# schematic.net
KiCad netlist of a schematic drawn in EAGLE
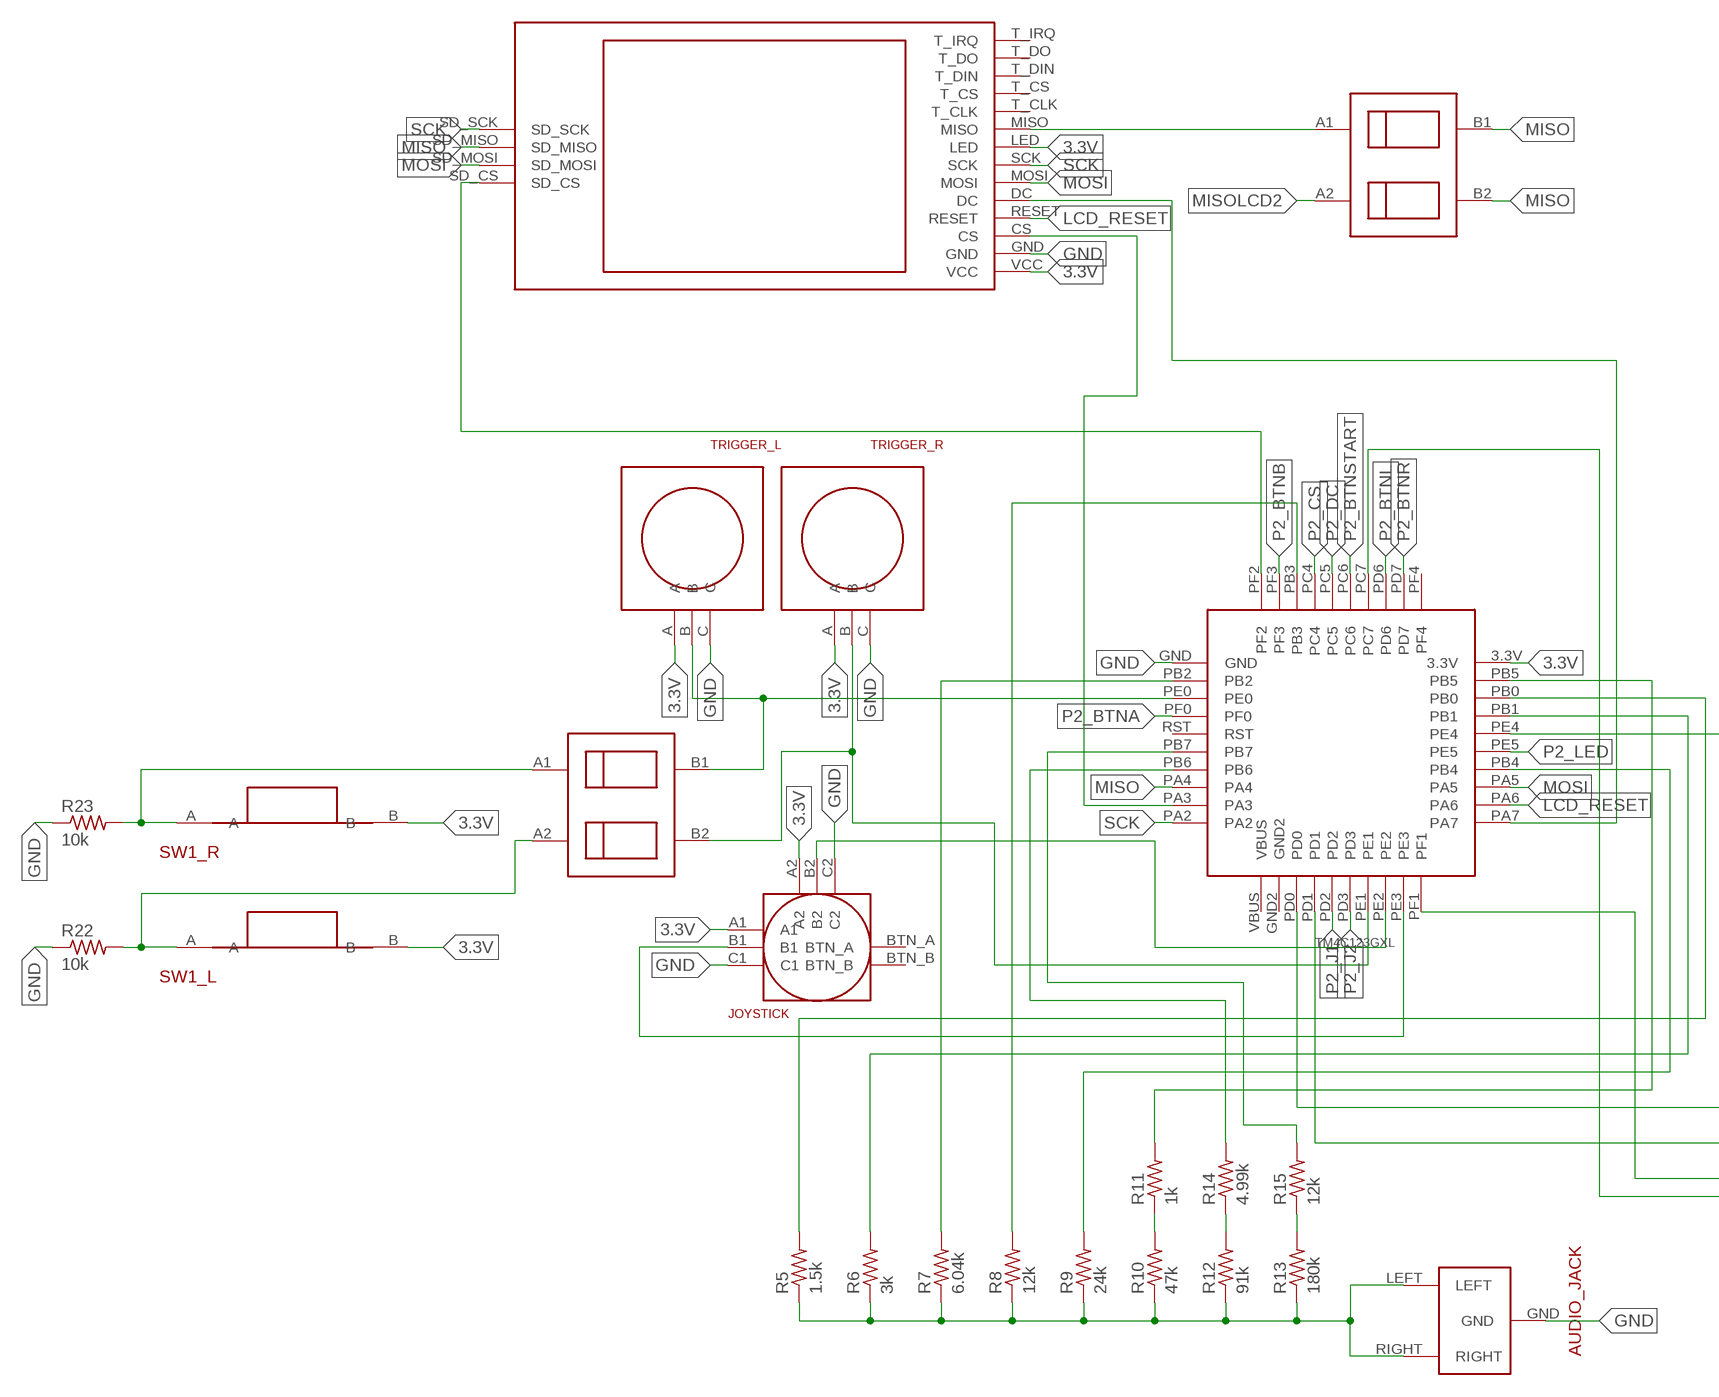
[diagram p0: schematic, sheet 1, part 1 of 2]
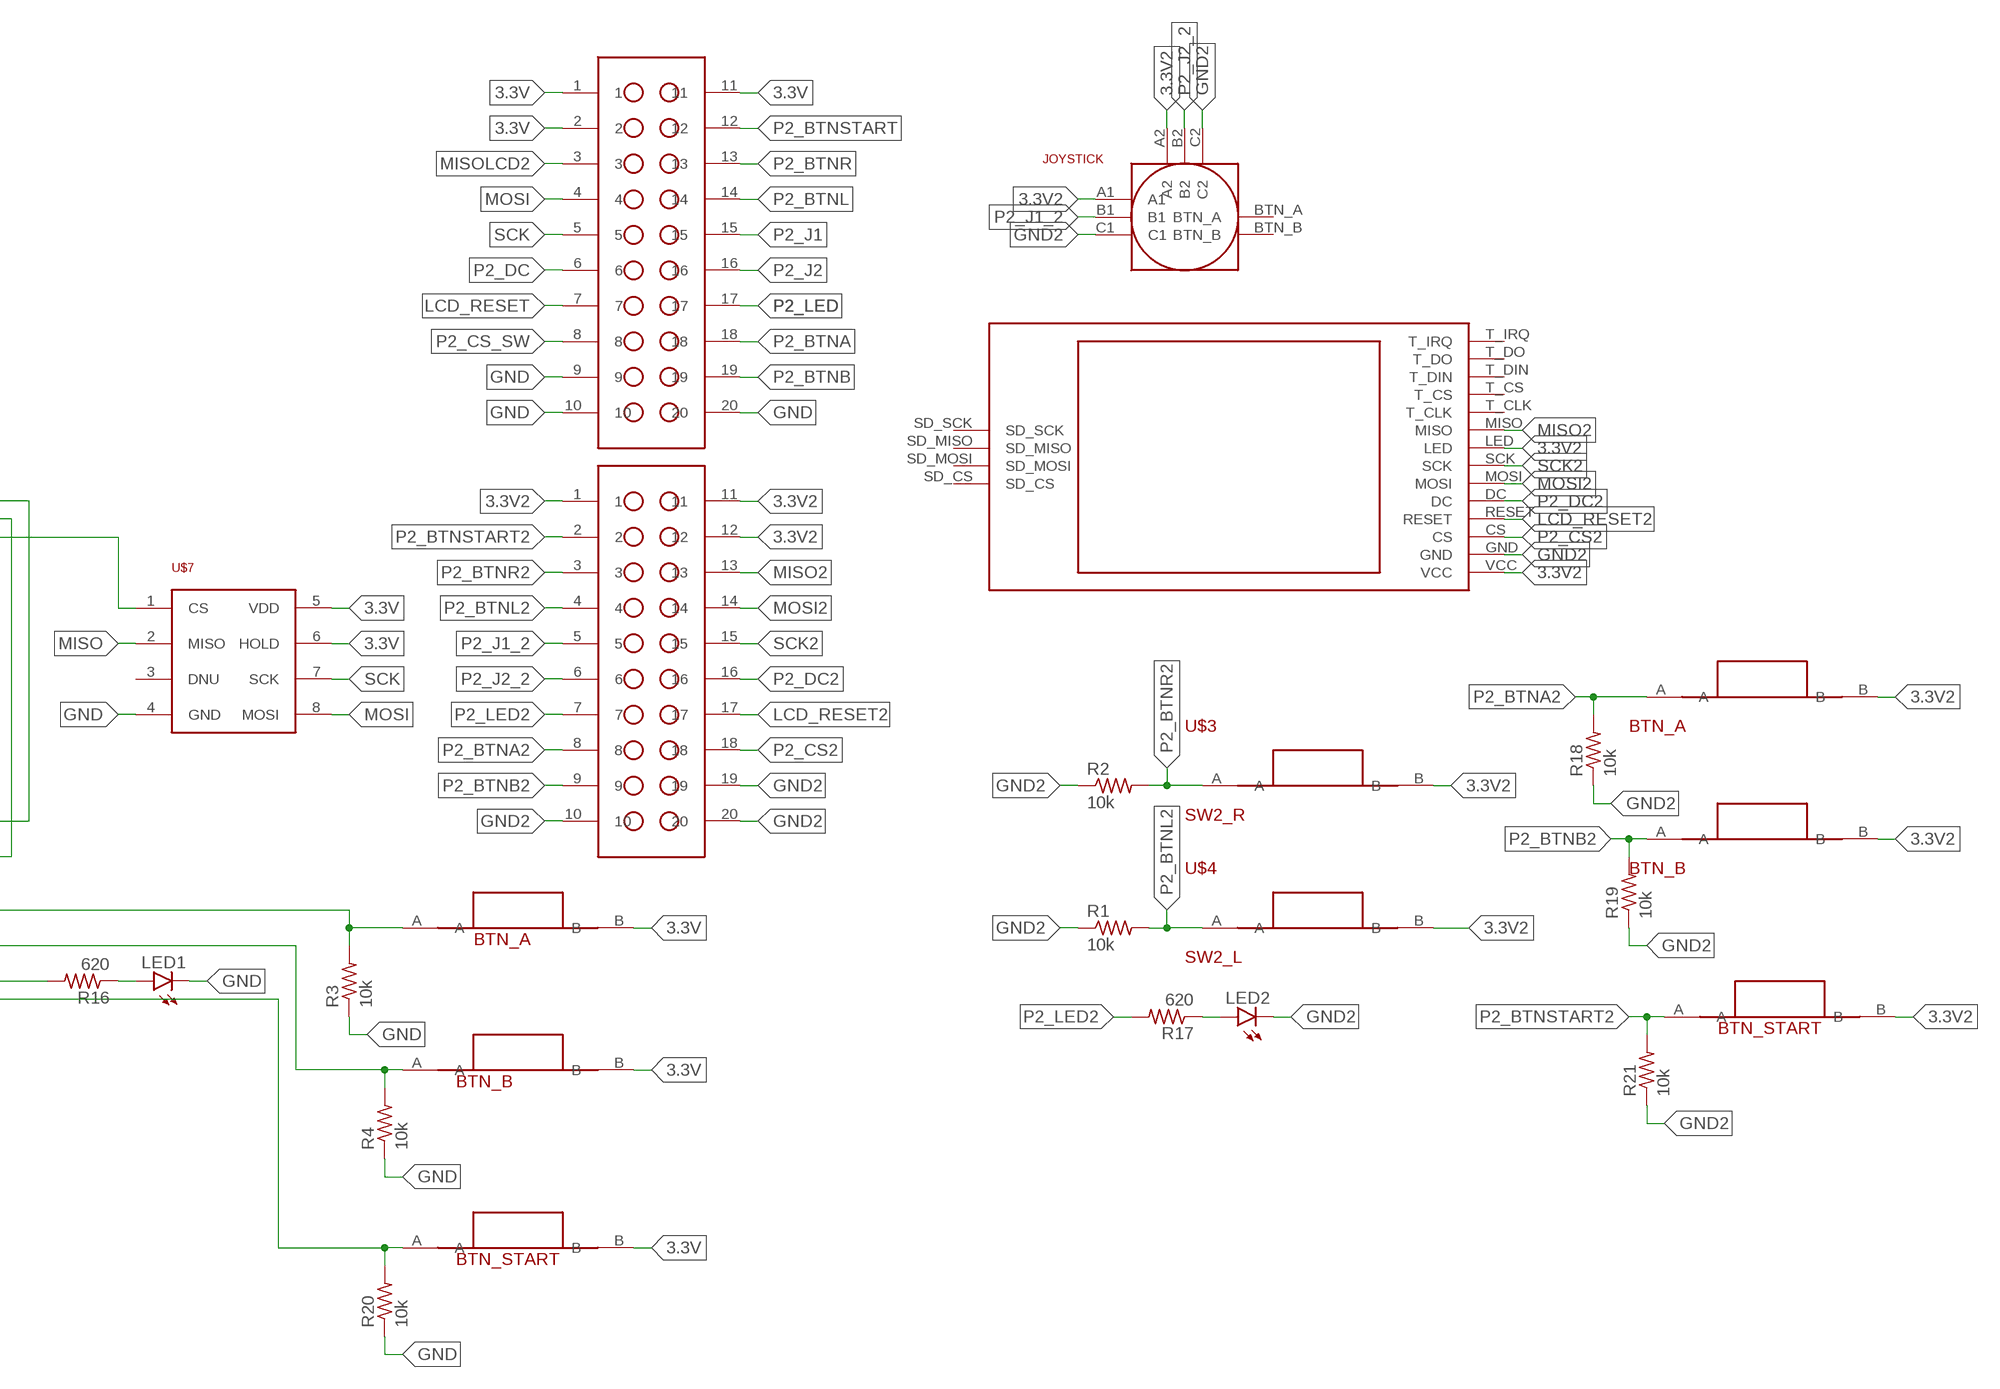
[diagram p1: schematic, sheet 1, part 2 of 2]

(export (version "E")
  (design (tool "Eeschema 10.0.6"))
  (components
    (comp (ref "LED1")
      (value "LEDCHIPLED_1206")
      (footprint "eagle-import:CHIPLED_1206")
      (libsource (lib "eagle-import") (part "LEDCHIPLED_1206"))
    )
    (comp (ref "LED2")
      (value "LEDCHIPLED_1206")
      (footprint "eagle-import:CHIPLED_1206")
      (libsource (lib "eagle-import") (part "LEDCHIPLED_1206"))
    )
    (comp (ref "P1_LCD")
      (value "ILI9341")
      (footprint "eagle-import:ILI9341")
      (libsource (lib "eagle-import") (part "ILI9341"))
    )
    (comp (ref "P2_LCD")
      (value "ILI9341")
      (footprint "eagle-import:ILI9341")
      (libsource (lib "eagle-import") (part "ILI9341"))
    )
    (comp (ref "R1")
      (value "10k")
      (footprint "eagle-import:R0805")
      (libsource (lib "eagle-import") (part "R-US_R0805"))
    )
    (comp (ref "R2")
      (value "10k")
      (footprint "eagle-import:R0805")
      (libsource (lib "eagle-import") (part "R-US_R0805"))
    )
    (comp (ref "R3")
      (value "10k")
      (footprint "eagle-import:R0805")
      (libsource (lib "eagle-import") (part "R-US_R0805"))
    )
    (comp (ref "R4")
      (value "10k")
      (footprint "eagle-import:R0805")
      (libsource (lib "eagle-import") (part "R-US_R0805"))
    )
    (comp (ref "R5")
      (value "1.5k")
      (footprint "eagle-import:R0805")
      (libsource (lib "eagle-import") (part "R-US_R0805"))
    )
    (comp (ref "R6")
      (value "3k")
      (footprint "eagle-import:R0805")
      (libsource (lib "eagle-import") (part "R-US_R0805"))
    )
    (comp (ref "R7")
      (value "6.04k")
      (footprint "eagle-import:R0805")
      (libsource (lib "eagle-import") (part "R-US_R0805"))
    )
    (comp (ref "R8")
      (value "12k")
      (footprint "eagle-import:R0805")
      (libsource (lib "eagle-import") (part "R-US_R0805"))
    )
    (comp (ref "R9")
      (value "24k")
      (footprint "eagle-import:R0805")
      (libsource (lib "eagle-import") (part "R-US_R0805"))
    )
    (comp (ref "R10")
      (value "47k")
      (footprint "eagle-import:R0805")
      (libsource (lib "eagle-import") (part "R-US_R0805"))
    )
    (comp (ref "R11")
      (value "1k")
      (footprint "eagle-import:R0805")
      (libsource (lib "eagle-import") (part "R-US_R0805"))
    )
    (comp (ref "R12")
      (value "91k")
      (footprint "eagle-import:R0805")
      (libsource (lib "eagle-import") (part "R-US_R0805"))
    )
    (comp (ref "R13")
      (value "180k")
      (footprint "eagle-import:R0805")
      (libsource (lib "eagle-import") (part "R-US_R0805"))
    )
    (comp (ref "R14")
      (value "4.99k")
      (footprint "eagle-import:R0805")
      (libsource (lib "eagle-import") (part "R-US_R0805"))
    )
    (comp (ref "R15")
      (value "12k")
      (footprint "eagle-import:R0805")
      (libsource (lib "eagle-import") (part "R-US_R0805"))
    )
    (comp (ref "R16")
      (value "620")
      (footprint "eagle-import:R0805")
      (libsource (lib "eagle-import") (part "R-US_R0805"))
    )
    (comp (ref "R17")
      (value "620")
      (footprint "eagle-import:R0805")
      (libsource (lib "eagle-import") (part "R-US_R0805"))
    )
    (comp (ref "R18")
      (value "10k")
      (footprint "eagle-import:R0805")
      (libsource (lib "eagle-import") (part "R-US_R0805"))
    )
    (comp (ref "R19")
      (value "10k")
      (footprint "eagle-import:R0805")
      (libsource (lib "eagle-import") (part "R-US_R0805"))
    )
    (comp (ref "R20")
      (value "10k")
      (footprint "eagle-import:R0805")
      (libsource (lib "eagle-import") (part "R-US_R0805"))
    )
    (comp (ref "R21")
      (value "10k")
      (footprint "eagle-import:R0805")
      (libsource (lib "eagle-import") (part "R-US_R0805"))
    )
    (comp (ref "R22")
      (value "10k")
      (footprint "eagle-import:R0805")
      (libsource (lib "eagle-import") (part "R-US_R0805"))
    )
    (comp (ref "R23")
      (value "10k")
      (footprint "eagle-import:R0805")
      (libsource (lib "eagle-import") (part "R-US_R0805"))
    )
    (comp (ref "U$1")
      (value "TM4C123GXL")
      (footprint "eagle-import:TM4C123GXL")
      (libsource (lib "eagle-import") (part "TM4C123GXL"))
    )
    (comp (ref "U$2")
      (value "JOYSTICK")
      (footprint "eagle-import:JOYSTICK")
      (libsource (lib "eagle-import") (part "JOYSTICK"))
    )
    (comp (ref "U$3")
      (value "SW2_R")
      (footprint "eagle-import:SW-1825968-2")
      (libsource (lib "eagle-import") (part "SW-1825968-2"))
    )
    (comp (ref "U$4")
      (value "SW2_L")
      (footprint "eagle-import:SW-1825968-2")
      (libsource (lib "eagle-import") (part "SW-1825968-2"))
    )
    (comp (ref "U$5")
      (value "TRIGGER_L")
      (footprint "eagle-import:TRIGGER_L")
      (libsource (lib "eagle-import") (part "TRIGGER_L"))
    )
    (comp (ref "U$6")
      (value "TRIGGER_R")
      (footprint "eagle-import:TRIGGER_R")
      (libsource (lib "eagle-import") (part "TRIGGER_R"))
    )
    (comp (ref "U$7")
      (value "IS62WVS5128FALL-16NLI")
      (footprint "eagle-import:SOIC127P600X144-8")
      (libsource (lib "eagle-import") (part "IS62WVS5128FALL-16NLI"))
    )
    (comp (ref "U$8")
      (value "BTN_A")
      (footprint "eagle-import:BUTTON")
      (libsource (lib "eagle-import") (part "BUTTON"))
    )
    (comp (ref "U$9")
      (value "BTN_B")
      (footprint "eagle-import:BUTTON")
      (libsource (lib "eagle-import") (part "BUTTON"))
    )
    (comp (ref "U$10")
      (value "AUDIO_JACK")
      (footprint "eagle-import:AUDIO_JACK")
      (libsource (lib "eagle-import") (part "AUDIO_JACK"))
    )
    (comp (ref "U$11")
      (value "10X2_HEADER")
      (footprint "eagle-import:10X2_HEADER")
      (libsource (lib "eagle-import") (part "10X2_HEADER"))
    )
    (comp (ref "U$12")
      (value "10X2_HEADER")
      (footprint "eagle-import:10X2_HEADER")
      (libsource (lib "eagle-import") (part "10X2_HEADER"))
    )
    (comp (ref "U$13")
      (value "JOYSTICK")
      (footprint "eagle-import:JOYSTICK")
      (libsource (lib "eagle-import") (part "JOYSTICK"))
    )
    (comp (ref "U$14")
      (value "BTN_A")
      (footprint "eagle-import:BUTTON")
      (libsource (lib "eagle-import") (part "BUTTON"))
    )
    (comp (ref "U$15")
      (value "BTN_B")
      (footprint "eagle-import:BUTTON")
      (libsource (lib "eagle-import") (part "BUTTON"))
    )
    (comp (ref "U$16")
      (value "BTN_START")
      (footprint "eagle-import:BUTTON")
      (libsource (lib "eagle-import") (part "BUTTON"))
    )
    (comp (ref "U$17")
      (value "BTN_START")
      (footprint "eagle-import:BUTTON")
      (libsource (lib "eagle-import") (part "BUTTON"))
    )
    (comp (ref "U$18")
      (value "SW1_R")
      (footprint "eagle-import:SW-1825968-2")
      (libsource (lib "eagle-import") (part "SW-1825968-2"))
    )
    (comp (ref "U$19")
      (value "SW1_L")
      (footprint "eagle-import:SW-1825968-2")
      (libsource (lib "eagle-import") (part "SW-1825968-2"))
    )
    (comp (ref "U$20")
      (value "DIPSW-2")
      (footprint "eagle-import:DIPSW-2")
      (libsource (lib "eagle-import") (part "DIPSW-2"))
    )
    (comp (ref "U$21")
      (value "DIPSW-2")
      (footprint "eagle-import:DIPSW-2")
      (libsource (lib "eagle-import") (part "DIPSW-2"))
    )
  )
  (nets
    (net (code "1") (name "3.3V") (class "Default")
      (node (ref "P1_LCD") (pin "LED") (pinfunction "LED_LED") (pintype "bidirectional"))
      (node (ref "P1_LCD") (pin "VCC") (pinfunction "VCC_VCC") (pintype "bidirectional"))
      (node (ref "U$1") (pin "3.3V") (pinfunction "3.3V_3.3V") (pintype "bidirectional"))
      (node (ref "U$11") (pin "1") (pinfunction "1_1") (pintype "bidirectional"))
      (node (ref "U$11") (pin "11") (pinfunction "11_11") (pintype "bidirectional"))
      (node (ref "U$11") (pin "2") (pinfunction "2_2") (pintype "bidirectional"))
      (node (ref "U$16") (pin "B") (pinfunction "B_B") (pintype "bidirectional"))
      (node (ref "U$18") (pin "B") (pinfunction "B_B") (pintype "bidirectional"))
      (node (ref "U$19") (pin "B") (pinfunction "B_B") (pintype "bidirectional"))
      (node (ref "U$2") (pin "A1") (pinfunction "A1_A1") (pintype "bidirectional"))
      (node (ref "U$2") (pin "A2") (pinfunction "A2_A2") (pintype "bidirectional"))
      (node (ref "U$5") (pin "A") (pinfunction "A_A") (pintype "bidirectional"))
      (node (ref "U$6") (pin "A") (pinfunction "A_A") (pintype "bidirectional"))
      (node (ref "U$7") (pin "5") (pinfunction "VDD_5") (pintype "bidirectional"))
      (node (ref "U$7") (pin "6") (pinfunction "HOLD_6") (pintype "bidirectional"))
      (node (ref "U$8") (pin "B") (pinfunction "B_B") (pintype "bidirectional"))
      (node (ref "U$9") (pin "B") (pinfunction "B_B") (pintype "bidirectional"))
    )
    (net (code "2") (name "3.3V2") (class "Default")
      (node (ref "P2_LCD") (pin "LED") (pinfunction "LED_LED") (pintype "bidirectional"))
      (node (ref "P2_LCD") (pin "VCC") (pinfunction "VCC_VCC") (pintype "bidirectional"))
      (node (ref "U$12") (pin "1") (pinfunction "1_1") (pintype "bidirectional"))
      (node (ref "U$12") (pin "11") (pinfunction "11_11") (pintype "bidirectional"))
      (node (ref "U$12") (pin "12") (pinfunction "12_12") (pintype "bidirectional"))
      (node (ref "U$13") (pin "A1") (pinfunction "A1_A1") (pintype "bidirectional"))
      (node (ref "U$13") (pin "A2") (pinfunction "A2_A2") (pintype "bidirectional"))
      (node (ref "U$14") (pin "B") (pinfunction "B_B") (pintype "bidirectional"))
      (node (ref "U$15") (pin "B") (pinfunction "B_B") (pintype "bidirectional"))
      (node (ref "U$17") (pin "B") (pinfunction "B_B") (pintype "bidirectional"))
      (node (ref "U$3") (pin "B") (pinfunction "B_B") (pintype "bidirectional"))
      (node (ref "U$4") (pin "B") (pinfunction "B_B") (pintype "bidirectional"))
    )
    (net (code "3") (name "GND") (class "Default")
      (node (ref "LED1") (pin "C") (pinfunction "C_C") (pintype "passive"))
      (node (ref "P1_LCD") (pin "GND") (pinfunction "GND_GND") (pintype "bidirectional"))
      (node (ref "R20") (pin "1") (pinfunction "1_1") (pintype "passive"))
      (node (ref "R22") (pin "1") (pinfunction "1_1") (pintype "passive"))
      (node (ref "R23") (pin "1") (pinfunction "1_1") (pintype "passive"))
      (node (ref "R3") (pin "1") (pinfunction "1_1") (pintype "passive"))
      (node (ref "R4") (pin "1") (pinfunction "1_1") (pintype "passive"))
      (node (ref "U$1") (pin "GND") (pinfunction "GND_GND") (pintype "bidirectional"))
      (node (ref "U$10") (pin "GND") (pinfunction "GND_GND") (pintype "bidirectional"))
      (node (ref "U$11") (pin "10") (pinfunction "10_10") (pintype "bidirectional"))
      (node (ref "U$11") (pin "20") (pinfunction "20_20") (pintype "bidirectional"))
      (node (ref "U$11") (pin "9") (pinfunction "9_9") (pintype "bidirectional"))
      (node (ref "U$2") (pin "C1") (pinfunction "C1_C1") (pintype "bidirectional"))
      (node (ref "U$2") (pin "C2") (pinfunction "C2_C2") (pintype "bidirectional"))
      (node (ref "U$5") (pin "C") (pinfunction "C_C") (pintype "bidirectional"))
      (node (ref "U$6") (pin "C") (pinfunction "C_C") (pintype "bidirectional"))
      (node (ref "U$7") (pin "4") (pinfunction "GND_4") (pintype "bidirectional"))
    )
    (net (code "4") (name "GND2") (class "Default")
      (node (ref "LED2") (pin "C") (pinfunction "C_C") (pintype "passive"))
      (node (ref "P2_LCD") (pin "GND") (pinfunction "GND_GND") (pintype "bidirectional"))
      (node (ref "R1") (pin "1") (pinfunction "1_1") (pintype "passive"))
      (node (ref "R18") (pin "1") (pinfunction "1_1") (pintype "passive"))
      (node (ref "R19") (pin "1") (pinfunction "1_1") (pintype "passive"))
      (node (ref "R2") (pin "1") (pinfunction "1_1") (pintype "passive"))
      (node (ref "R21") (pin "1") (pinfunction "1_1") (pintype "passive"))
      (node (ref "U$12") (pin "10") (pinfunction "10_10") (pintype "bidirectional"))
      (node (ref "U$12") (pin "19") (pinfunction "19_19") (pintype "bidirectional"))
      (node (ref "U$12") (pin "20") (pinfunction "20_20") (pintype "bidirectional"))
      (node (ref "U$13") (pin "C1") (pinfunction "C1_C1") (pintype "bidirectional"))
      (node (ref "U$13") (pin "C2") (pinfunction "C2_C2") (pintype "bidirectional"))
    )
    (net (code "5") (name "LCD_RESET") (class "Default")
      (node (ref "P1_LCD") (pin "RESET") (pinfunction "RESET_RESET") (pintype "bidirectional"))
      (node (ref "U$1") (pin "PA6") (pinfunction "PA6_PA6") (pintype "bidirectional"))
      (node (ref "U$11") (pin "7") (pinfunction "7_7") (pintype "bidirectional"))
    )
    (net (code "6") (name "LCD_RESET2") (class "Default")
      (node (ref "P2_LCD") (pin "RESET") (pinfunction "RESET_RESET") (pintype "bidirectional"))
      (node (ref "U$12") (pin "17") (pinfunction "17_17") (pintype "bidirectional"))
    )
    (net (code "7") (name "MISO") (class "Default")
      (node (ref "P1_LCD") (pin "SD_MISO") (pinfunction "SD_MISO_SD_MISO") (pintype "bidirectional"))
      (node (ref "U$1") (pin "PA4") (pinfunction "PA4_PA4") (pintype "bidirectional"))
      (node (ref "U$21") (pin "B1") (pinfunction "B1_B1") (pintype "passive"))
      (node (ref "U$21") (pin "B2") (pinfunction "B2_B2") (pintype "passive"))
      (node (ref "U$7") (pin "2") (pinfunction "MISO_2") (pintype "bidirectional"))
    )
    (net (code "8") (name "MISO2") (class "Default")
      (node (ref "P2_LCD") (pin "MISO") (pinfunction "MISO_MISO") (pintype "bidirectional"))
      (node (ref "U$12") (pin "13") (pinfunction "13_13") (pintype "bidirectional"))
    )
    (net (code "9") (name "MISOLCD2") (class "Default")
      (node (ref "U$11") (pin "3") (pinfunction "3_3") (pintype "bidirectional"))
      (node (ref "U$21") (pin "A2") (pinfunction "A2_A2") (pintype "passive"))
    )
    (net (code "10") (name "MOSI") (class "Default")
      (node (ref "P1_LCD") (pin "MOSI") (pinfunction "MOSI_MOSI") (pintype "bidirectional"))
      (node (ref "P1_LCD") (pin "SD_MOSI") (pinfunction "SD_MOSI_SD_MOSI") (pintype "bidirectional"))
      (node (ref "U$1") (pin "PA5") (pinfunction "PA5_PA5") (pintype "bidirectional"))
      (node (ref "U$11") (pin "4") (pinfunction "4_4") (pintype "bidirectional"))
      (node (ref "U$7") (pin "8") (pinfunction "MOSI_8") (pintype "bidirectional"))
    )
    (net (code "11") (name "MOSI2") (class "Default")
      (node (ref "P2_LCD") (pin "MOSI") (pinfunction "MOSI_MOSI") (pintype "bidirectional"))
      (node (ref "U$12") (pin "14") (pinfunction "14_14") (pintype "bidirectional"))
    )
    (net (code "12") (name "Net-(LED1-PadA)") (class "Default")
      (node (ref "LED1") (pin "A") (pinfunction "A_A") (pintype "passive"))
      (node (ref "R16") (pin "1") (pinfunction "1_1") (pintype "passive"))
    )
    (net (code "13") (name "Net-(LED2-PadA)") (class "Default")
      (node (ref "LED2") (pin "A") (pinfunction "A_A") (pintype "passive"))
      (node (ref "R17") (pin "1") (pinfunction "1_1") (pintype "passive"))
    )
    (net (code "14") (name "Net-(P1_LCD-PadCS)") (class "Default")
      (node (ref "P1_LCD") (pin "CS") (pinfunction "CS_CS") (pintype "bidirectional"))
      (node (ref "U$1") (pin "PA3") (pinfunction "PA3_PA3") (pintype "bidirectional"))
    )
    (net (code "15") (name "Net-(P1_LCD-PadDC)") (class "Default")
      (node (ref "P1_LCD") (pin "DC") (pinfunction "DC_DC") (pintype "bidirectional"))
      (node (ref "U$1") (pin "PA7") (pinfunction "PA7_PA7") (pintype "bidirectional"))
    )
    (net (code "16") (name "Net-(P1_LCD-PadMISO)") (class "Default")
      (node (ref "P1_LCD") (pin "MISO") (pinfunction "MISO_MISO") (pintype "bidirectional"))
      (node (ref "U$21") (pin "A1") (pinfunction "A1_A1") (pintype "passive"))
    )
    (net (code "17") (name "Net-(P1_LCD-PadSD_CS)") (class "Default")
      (node (ref "P1_LCD") (pin "SD_CS") (pinfunction "SD_CS_SD_CS") (pintype "bidirectional"))
      (node (ref "U$1") (pin "PF2") (pinfunction "PF2_PF2") (pintype "bidirectional"))
    )
    (net (code "18") (name "Net-(R3-Pad2)") (class "Default")
      (node (ref "R3") (pin "2") (pinfunction "2_2") (pintype "passive"))
      (node (ref "U$1") (pin "PD0") (pinfunction "PD0_PD0") (pintype "bidirectional"))
      (node (ref "U$8") (pin "A") (pinfunction "A_A") (pintype "bidirectional"))
    )
    (net (code "19") (name "Net-(R4-Pad2)") (class "Default")
      (node (ref "R4") (pin "2") (pinfunction "2_2") (pintype "passive"))
      (node (ref "U$1") (pin "PD1") (pinfunction "PD1_PD1") (pintype "bidirectional"))
      (node (ref "U$9") (pin "A") (pinfunction "A_A") (pintype "bidirectional"))
    )
    (net (code "20") (name "Net-(R5-Pad2)") (class "Default")
      (node (ref "R5") (pin "2") (pinfunction "2_2") (pintype "passive"))
      (node (ref "U$1") (pin "PB0") (pinfunction "PB0_PB0") (pintype "bidirectional"))
    )
    (net (code "21") (name "Net-(R6-Pad2)") (class "Default")
      (node (ref "R6") (pin "2") (pinfunction "2_2") (pintype "passive"))
      (node (ref "U$1") (pin "PB1") (pinfunction "PB1_PB1") (pintype "bidirectional"))
    )
    (net (code "22") (name "Net-(R7-Pad2)") (class "Default")
      (node (ref "R7") (pin "2") (pinfunction "2_2") (pintype "passive"))
      (node (ref "U$1") (pin "PB2") (pinfunction "PB2_PB2") (pintype "bidirectional"))
    )
    (net (code "23") (name "Net-(R8-Pad2)") (class "Default")
      (node (ref "R8") (pin "2") (pinfunction "2_2") (pintype "passive"))
      (node (ref "U$1") (pin "PB3") (pinfunction "PB3_PB3") (pintype "bidirectional"))
    )
    (net (code "24") (name "Net-(R9-Pad2)") (class "Default")
      (node (ref "R9") (pin "2") (pinfunction "2_2") (pintype "passive"))
      (node (ref "U$1") (pin "PB4") (pinfunction "PB4_PB4") (pintype "bidirectional"))
    )
    (net (code "25") (name "Net-(R10-Pad1)") (class "Default")
      (node (ref "R10") (pin "1") (pinfunction "1_1") (pintype "passive"))
      (node (ref "R12") (pin "1") (pinfunction "1_1") (pintype "passive"))
      (node (ref "R13") (pin "1") (pinfunction "1_1") (pintype "passive"))
      (node (ref "R5") (pin "1") (pinfunction "1_1") (pintype "passive"))
      (node (ref "R6") (pin "1") (pinfunction "1_1") (pintype "passive"))
      (node (ref "R7") (pin "1") (pinfunction "1_1") (pintype "passive"))
      (node (ref "R8") (pin "1") (pinfunction "1_1") (pintype "passive"))
      (node (ref "R9") (pin "1") (pinfunction "1_1") (pintype "passive"))
      (node (ref "U$10") (pin "LEFT") (pinfunction "LEFT_LEFT") (pintype "bidirectional"))
      (node (ref "U$10") (pin "RIGHT") (pinfunction "RIGHT_RIGHT") (pintype "bidirectional"))
    )
    (net (code "26") (name "Net-(R10-Pad2)") (class "Default")
      (node (ref "R10") (pin "2") (pinfunction "2_2") (pintype "passive"))
      (node (ref "R11") (pin "1") (pinfunction "1_1") (pintype "passive"))
    )
    (net (code "27") (name "Net-(R11-Pad2)") (class "Default")
      (node (ref "R11") (pin "2") (pinfunction "2_2") (pintype "passive"))
      (node (ref "U$1") (pin "PB5") (pinfunction "PB5_PB5") (pintype "bidirectional"))
    )
    (net (code "28") (name "Net-(R12-Pad2)") (class "Default")
      (node (ref "R12") (pin "2") (pinfunction "2_2") (pintype "passive"))
      (node (ref "R14") (pin "1") (pinfunction "1_1") (pintype "passive"))
    )
    (net (code "29") (name "Net-(R13-Pad2)") (class "Default")
      (node (ref "R13") (pin "2") (pinfunction "2_2") (pintype "passive"))
      (node (ref "R15") (pin "1") (pinfunction "1_1") (pintype "passive"))
    )
    (net (code "30") (name "Net-(R14-Pad2)") (class "Default")
      (node (ref "R14") (pin "2") (pinfunction "2_2") (pintype "passive"))
      (node (ref "U$1") (pin "PB6") (pinfunction "PB6_PB6") (pintype "bidirectional"))
    )
    (net (code "31") (name "Net-(R15-Pad2)") (class "Default")
      (node (ref "R15") (pin "2") (pinfunction "2_2") (pintype "passive"))
      (node (ref "U$1") (pin "PB7") (pinfunction "PB7_PB7") (pintype "bidirectional"))
    )
    (net (code "32") (name "Net-(R16-Pad2)") (class "Default")
      (node (ref "R16") (pin "2") (pinfunction "2_2") (pintype "passive"))
      (node (ref "U$1") (pin "PF1") (pinfunction "PF1_PF1") (pintype "bidirectional"))
    )
    (net (code "33") (name "Net-(R20-Pad2)") (class "Default")
      (node (ref "R20") (pin "2") (pinfunction "2_2") (pintype "passive"))
      (node (ref "U$1") (pin "PC7") (pinfunction "PC7_PC7") (pintype "bidirectional"))
      (node (ref "U$16") (pin "A") (pinfunction "A_A") (pintype "bidirectional"))
    )
    (net (code "34") (name "Net-(R22-Pad2)") (class "Default")
      (node (ref "R22") (pin "2") (pinfunction "2_2") (pintype "passive"))
      (node (ref "U$19") (pin "A") (pinfunction "A_A") (pintype "bidirectional"))
      (node (ref "U$20") (pin "A2") (pinfunction "A2_A2") (pintype "passive"))
    )
    (net (code "35") (name "Net-(R23-Pad2)") (class "Default")
      (node (ref "R23") (pin "2") (pinfunction "2_2") (pintype "passive"))
      (node (ref "U$18") (pin "A") (pinfunction "A_A") (pintype "bidirectional"))
      (node (ref "U$20") (pin "A1") (pinfunction "A1_A1") (pintype "passive"))
    )
    (net (code "36") (name "Net-(U$1-PadPE0)") (class "Default")
      (node (ref "U$1") (pin "PE0") (pinfunction "PE0_PE0") (pintype "bidirectional"))
      (node (ref "U$20") (pin "B1") (pinfunction "B1_B1") (pintype "passive"))
      (node (ref "U$5") (pin "B") (pinfunction "B_B") (pintype "bidirectional"))
    )
    (net (code "37") (name "Net-(U$1-PadPE1)") (class "Default")
      (node (ref "U$1") (pin "PE1") (pinfunction "PE1_PE1") (pintype "bidirectional"))
      (node (ref "U$20") (pin "B2") (pinfunction "B2_B2") (pintype "passive"))
      (node (ref "U$6") (pin "B") (pinfunction "B_B") (pintype "bidirectional"))
    )
    (net (code "38") (name "Net-(U$1-PadPE2)") (class "Default")
      (node (ref "U$1") (pin "PE2") (pinfunction "PE2_PE2") (pintype "bidirectional"))
      (node (ref "U$2") (pin "B2") (pinfunction "B2_B2") (pintype "bidirectional"))
    )
    (net (code "39") (name "Net-(U$1-PadPE3)") (class "Default")
      (node (ref "U$1") (pin "PE3") (pinfunction "PE3_PE3") (pintype "bidirectional"))
      (node (ref "U$2") (pin "B1") (pinfunction "B1_B1") (pintype "bidirectional"))
    )
    (net (code "40") (name "Net-(U$7-CS)") (class "Default")
      (node (ref "U$1") (pin "PE4") (pinfunction "PE4_PE4") (pintype "bidirectional"))
      (node (ref "U$7") (pin "1") (pinfunction "CS_1") (pintype "bidirectional"))
    )
    (net (code "41") (name "P2_BTNA") (class "Default")
      (node (ref "U$1") (pin "PF0") (pinfunction "PF0_PF0") (pintype "bidirectional"))
      (node (ref "U$11") (pin "18") (pinfunction "18_18") (pintype "bidirectional"))
    )
    (net (code "42") (name "P2_BTNA2") (class "Default")
      (node (ref "R18") (pin "2") (pinfunction "2_2") (pintype "passive"))
      (node (ref "U$12") (pin "8") (pinfunction "8_8") (pintype "bidirectional"))
      (node (ref "U$14") (pin "A") (pinfunction "A_A") (pintype "bidirectional"))
    )
    (net (code "43") (name "P2_BTNB") (class "Default")
      (node (ref "U$1") (pin "PF3") (pinfunction "PF3_PF3") (pintype "bidirectional"))
      (node (ref "U$11") (pin "19") (pinfunction "19_19") (pintype "bidirectional"))
    )
    (net (code "44") (name "P2_BTNB2") (class "Default")
      (node (ref "R19") (pin "2") (pinfunction "2_2") (pintype "passive"))
      (node (ref "U$12") (pin "9") (pinfunction "9_9") (pintype "bidirectional"))
      (node (ref "U$15") (pin "A") (pinfunction "A_A") (pintype "bidirectional"))
    )
    (net (code "45") (name "P2_BTNL") (class "Default")
      (node (ref "U$1") (pin "PD6") (pinfunction "PD6_PD6") (pintype "bidirectional"))
      (node (ref "U$11") (pin "14") (pinfunction "14_14") (pintype "bidirectional"))
    )
    (net (code "46") (name "P2_BTNL2") (class "Default")
      (node (ref "R1") (pin "2") (pinfunction "2_2") (pintype "passive"))
      (node (ref "U$12") (pin "4") (pinfunction "4_4") (pintype "bidirectional"))
      (node (ref "U$4") (pin "A") (pinfunction "A_A") (pintype "bidirectional"))
    )
    (net (code "47") (name "P2_BTNR") (class "Default")
      (node (ref "U$1") (pin "PD7") (pinfunction "PD7_PD7") (pintype "bidirectional"))
      (node (ref "U$11") (pin "13") (pinfunction "13_13") (pintype "bidirectional"))
    )
    (net (code "48") (name "P2_BTNR2") (class "Default")
      (node (ref "R2") (pin "2") (pinfunction "2_2") (pintype "passive"))
      (node (ref "U$12") (pin "3") (pinfunction "3_3") (pintype "bidirectional"))
      (node (ref "U$3") (pin "A") (pinfunction "A_A") (pintype "bidirectional"))
    )
    (net (code "49") (name "P2_BTNSTART") (class "Default")
      (node (ref "U$1") (pin "PC6") (pinfunction "PC6_PC6") (pintype "bidirectional"))
      (node (ref "U$11") (pin "12") (pinfunction "12_12") (pintype "bidirectional"))
    )
    (net (code "50") (name "P2_BTNSTART2") (class "Default")
      (node (ref "R21") (pin "2") (pinfunction "2_2") (pintype "passive"))
      (node (ref "U$12") (pin "2") (pinfunction "2_2") (pintype "bidirectional"))
      (node (ref "U$17") (pin "A") (pinfunction "A_A") (pintype "bidirectional"))
    )
    (net (code "51") (name "P2_CS") (class "Default")
      (node (ref "U$1") (pin "PC4") (pinfunction "PC4_PC4") (pintype "bidirectional"))
    )
    (net (code "52") (name "P2_CS2") (class "Default")
      (node (ref "P2_LCD") (pin "CS") (pinfunction "CS_CS") (pintype "bidirectional"))
      (node (ref "U$12") (pin "18") (pinfunction "18_18") (pintype "bidirectional"))
    )
    (net (code "53") (name "P2_CS_SW") (class "Default")
      (node (ref "U$11") (pin "8") (pinfunction "8_8") (pintype "bidirectional"))
    )
    (net (code "54") (name "P2_DC") (class "Default")
      (node (ref "U$1") (pin "PC5") (pinfunction "PC5_PC5") (pintype "bidirectional"))
      (node (ref "U$11") (pin "6") (pinfunction "6_6") (pintype "bidirectional"))
    )
    (net (code "55") (name "P2_DC2") (class "Default")
      (node (ref "P2_LCD") (pin "DC") (pinfunction "DC_DC") (pintype "bidirectional"))
      (node (ref "U$12") (pin "16") (pinfunction "16_16") (pintype "bidirectional"))
    )
    (net (code "56") (name "P2_J1") (class "Default")
      (node (ref "U$1") (pin "PD2") (pinfunction "PD2_PD2") (pintype "bidirectional"))
      (node (ref "U$11") (pin "15") (pinfunction "15_15") (pintype "bidirectional"))
    )
    (net (code "57") (name "P2_J1_2") (class "Default")
      (node (ref "U$12") (pin "5") (pinfunction "5_5") (pintype "bidirectional"))
      (node (ref "U$13") (pin "B1") (pinfunction "B1_B1") (pintype "bidirectional"))
    )
    (net (code "58") (name "P2_J2") (class "Default")
      (node (ref "U$1") (pin "PD3") (pinfunction "PD3_PD3") (pintype "bidirectional"))
      (node (ref "U$11") (pin "16") (pinfunction "16_16") (pintype "bidirectional"))
    )
    (net (code "59") (name "P2_J2_2") (class "Default")
      (node (ref "U$12") (pin "6") (pinfunction "6_6") (pintype "bidirectional"))
      (node (ref "U$13") (pin "B2") (pinfunction "B2_B2") (pintype "bidirectional"))
    )
    (net (code "60") (name "P2_LED") (class "Default")
      (node (ref "U$1") (pin "PE5") (pinfunction "PE5_PE5") (pintype "bidirectional"))
      (node (ref "U$11") (pin "17") (pinfunction "17_17") (pintype "bidirectional"))
    )
    (net (code "61") (name "P2_LED2") (class "Default")
      (node (ref "R17") (pin "2") (pinfunction "2_2") (pintype "passive"))
      (node (ref "U$12") (pin "7") (pinfunction "7_7") (pintype "bidirectional"))
    )
    (net (code "62") (name "SCK") (class "Default")
      (node (ref "P1_LCD") (pin "SCK") (pinfunction "SCK_SCK") (pintype "bidirectional"))
      (node (ref "P1_LCD") (pin "SD_SCK") (pinfunction "SD_SCK_SD_SCK") (pintype "bidirectional"))
      (node (ref "U$1") (pin "PA2") (pinfunction "PA2_PA2") (pintype "bidirectional"))
      (node (ref "U$11") (pin "5") (pinfunction "5_5") (pintype "bidirectional"))
      (node (ref "U$7") (pin "7") (pinfunction "SCK_7") (pintype "bidirectional"))
    )
    (net (code "63") (name "SCK2") (class "Default")
      (node (ref "P2_LCD") (pin "SCK") (pinfunction "SCK_SCK") (pintype "bidirectional"))
      (node (ref "U$12") (pin "15") (pinfunction "15_15") (pintype "bidirectional"))
    )
    (net (code "64") (name "unconnected-(P1_LCD-PadT_CLK)") (class "Default")
      (node (ref "P1_LCD") (pin "T_CLK") (pinfunction "T_CLK_T_CLK") (pintype "bidirectional"))
    )
    (net (code "65") (name "unconnected-(P1_LCD-PadT_CS)") (class "Default")
      (node (ref "P1_LCD") (pin "T_CS") (pinfunction "T_CS_T_CS") (pintype "bidirectional"))
    )
    (net (code "66") (name "unconnected-(P1_LCD-PadT_DIN)") (class "Default")
      (node (ref "P1_LCD") (pin "T_DIN") (pinfunction "T_DIN_T_DIN") (pintype "bidirectional"))
    )
    (net (code "67") (name "unconnected-(P1_LCD-PadT_DO)") (class "Default")
      (node (ref "P1_LCD") (pin "T_DO") (pinfunction "T_DO_T_DO") (pintype "bidirectional"))
    )
    (net (code "68") (name "unconnected-(P1_LCD-PadT_IRQ)") (class "Default")
      (node (ref "P1_LCD") (pin "T_IRQ") (pinfunction "T_IRQ_T_IRQ") (pintype "bidirectional"))
    )
    (net (code "69") (name "unconnected-(P2_LCD-PadSD_CS)") (class "Default")
      (node (ref "P2_LCD") (pin "SD_CS") (pinfunction "SD_CS_SD_CS") (pintype "bidirectional"))
    )
    (net (code "70") (name "unconnected-(P2_LCD-PadSD_MISO)") (class "Default")
      (node (ref "P2_LCD") (pin "SD_MISO") (pinfunction "SD_MISO_SD_MISO") (pintype "bidirectional"))
    )
    (net (code "71") (name "unconnected-(P2_LCD-PadSD_MOSI)") (class "Default")
      (node (ref "P2_LCD") (pin "SD_MOSI") (pinfunction "SD_MOSI_SD_MOSI") (pintype "bidirectional"))
    )
    (net (code "72") (name "unconnected-(P2_LCD-PadSD_SCK)") (class "Default")
      (node (ref "P2_LCD") (pin "SD_SCK") (pinfunction "SD_SCK_SD_SCK") (pintype "bidirectional"))
    )
    (net (code "73") (name "unconnected-(P2_LCD-PadT_CLK)") (class "Default")
      (node (ref "P2_LCD") (pin "T_CLK") (pinfunction "T_CLK_T_CLK") (pintype "bidirectional"))
    )
    (net (code "74") (name "unconnected-(P2_LCD-PadT_CS)") (class "Default")
      (node (ref "P2_LCD") (pin "T_CS") (pinfunction "T_CS_T_CS") (pintype "bidirectional"))
    )
    (net (code "75") (name "unconnected-(P2_LCD-PadT_DIN)") (class "Default")
      (node (ref "P2_LCD") (pin "T_DIN") (pinfunction "T_DIN_T_DIN") (pintype "bidirectional"))
    )
    (net (code "76") (name "unconnected-(P2_LCD-PadT_DO)") (class "Default")
      (node (ref "P2_LCD") (pin "T_DO") (pinfunction "T_DO_T_DO") (pintype "bidirectional"))
    )
    (net (code "77") (name "unconnected-(P2_LCD-PadT_IRQ)") (class "Default")
      (node (ref "P2_LCD") (pin "T_IRQ") (pinfunction "T_IRQ_T_IRQ") (pintype "bidirectional"))
    )
    (net (code "78") (name "unconnected-(U$1-PadGND2)") (class "Default")
      (node (ref "U$1") (pin "GND2") (pinfunction "GND2_GND2") (pintype "bidirectional"))
    )
    (net (code "79") (name "unconnected-(U$1-PadPF4)") (class "Default")
      (node (ref "U$1") (pin "PF4") (pinfunction "PF4_PF4") (pintype "bidirectional"))
    )
    (net (code "80") (name "unconnected-(U$1-PadRST)") (class "Default")
      (node (ref "U$1") (pin "RST") (pinfunction "RST_RST") (pintype "bidirectional"))
    )
    (net (code "81") (name "unconnected-(U$1-PadVBUS)") (class "Default")
      (node (ref "U$1") (pin "VBUS") (pinfunction "VBUS_VBUS") (pintype "bidirectional"))
    )
    (net (code "82") (name "unconnected-(U$2-PadBTN_A)") (class "Default")
      (node (ref "U$2") (pin "BTN_A") (pinfunction "BTN_A_BTN_A") (pintype "bidirectional"))
    )
    (net (code "83") (name "unconnected-(U$2-PadBTN_B)") (class "Default")
      (node (ref "U$2") (pin "BTN_B") (pinfunction "BTN_B_BTN_B") (pintype "bidirectional"))
    )
    (net (code "84") (name "unconnected-(U$7-DNU-Pad3)") (class "Default")
      (node (ref "U$7") (pin "3") (pinfunction "DNU_3") (pintype "bidirectional"))
    )
    (net (code "85") (name "unconnected-(U$13-PadBTN_A)") (class "Default")
      (node (ref "U$13") (pin "BTN_A") (pinfunction "BTN_A_BTN_A") (pintype "bidirectional"))
    )
    (net (code "86") (name "unconnected-(U$13-PadBTN_B)") (class "Default")
      (node (ref "U$13") (pin "BTN_B") (pinfunction "BTN_B_BTN_B") (pintype "bidirectional"))
    )
  )
)
